# ReactionGame.net
KiCad netlist of a schematic drawn in EAGLE
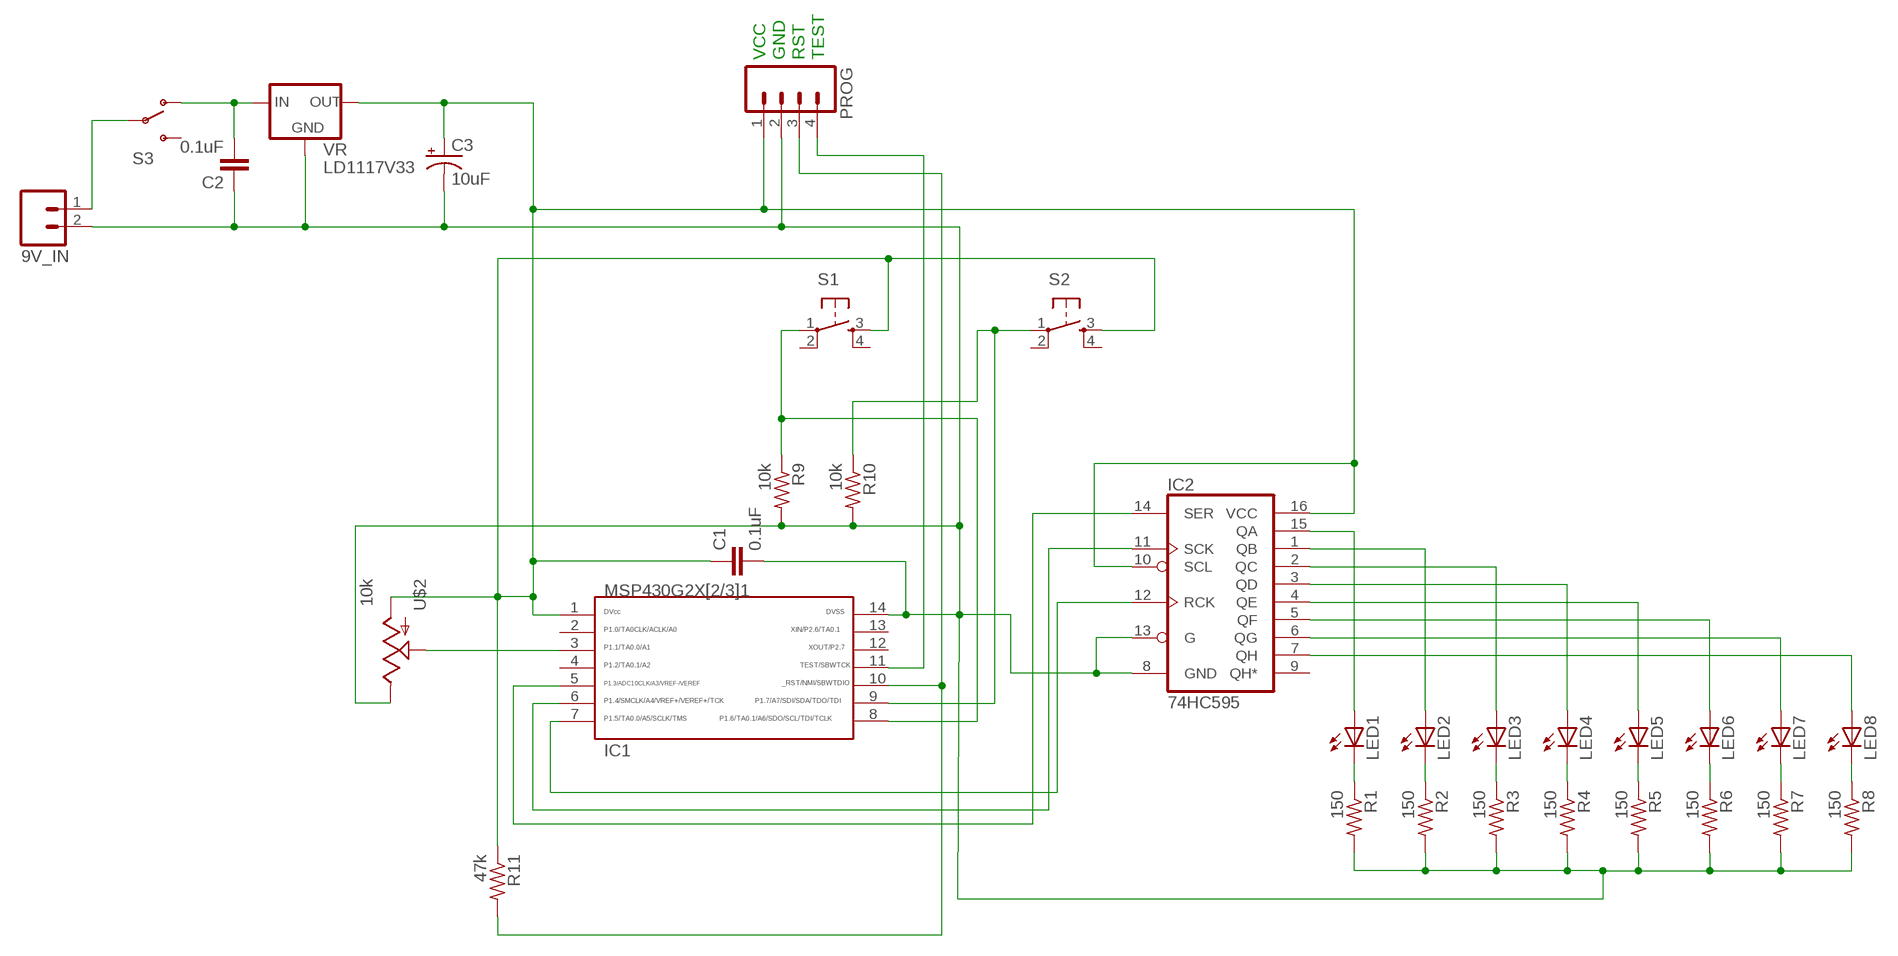
[diagram p0: schematic, sheet 1]

(export (version "E")
  (design (tool "Eeschema 10.0.6"))
  (components
    (comp (ref "9V_IN")
      (value "M02PTH3")
      (footprint "eagle-import:1X02_LONGPADS")
      (libsource (lib "eagle-import") (part "M02PTH3"))
    )
    (comp (ref "C1")
      (value "0.1uF")
      (footprint "eagle-import:CAP-PTH-SMALL2")
      (libsource (lib "eagle-import") (part "CAPPTH2"))
    )
    (comp (ref "C2")
      (value "0.1uF")
      (footprint "eagle-import:CAP-PTH-SMALL2")
      (libsource (lib "eagle-import") (part "CAPPTH2"))
    )
    (comp (ref "C3")
      (value "10uF")
      (footprint "eagle-import:CPOL-RADIAL-100UF-25V")
      (libsource (lib "eagle-import") (part "CAP_POLPTH1"))
    )
    (comp (ref "IC1")
      (value "MSP430G2231")
      (footprint "eagle-import:N14")
      (libsource (lib "eagle-import") (part "G2X[2/3]1---N14"))
    )
    (comp (ref "IC2")
      (value "74HC595")
      (footprint "eagle-import:DIL16")
      (libsource (lib "eagle-import") (part "74595NLS"))
    )
    (comp (ref "LED1")
      (value "LED5MM")
      (footprint "eagle-import:LED5MM")
      (libsource (lib "eagle-import") (part "LED5MM"))
    )
    (comp (ref "LED2")
      (value "LED5MM")
      (footprint "eagle-import:LED5MM")
      (libsource (lib "eagle-import") (part "LED5MM"))
    )
    (comp (ref "LED3")
      (value "LED5MM")
      (footprint "eagle-import:LED5MM")
      (libsource (lib "eagle-import") (part "LED5MM"))
    )
    (comp (ref "LED4")
      (value "LED5MM")
      (footprint "eagle-import:LED5MM")
      (libsource (lib "eagle-import") (part "LED5MM"))
    )
    (comp (ref "LED5")
      (value "LED5MM")
      (footprint "eagle-import:LED5MM")
      (libsource (lib "eagle-import") (part "LED5MM"))
    )
    (comp (ref "LED6")
      (value "LED5MM")
      (footprint "eagle-import:LED5MM")
      (libsource (lib "eagle-import") (part "LED5MM"))
    )
    (comp (ref "LED7")
      (value "LED5MM")
      (footprint "eagle-import:LED5MM")
      (libsource (lib "eagle-import") (part "LED5MM"))
    )
    (comp (ref "LED8")
      (value "LED5MM")
      (footprint "eagle-import:LED5MM")
      (libsource (lib "eagle-import") (part "LED5MM"))
    )
    (comp (ref "PROG")
      (value "M04LOCK")
      (footprint "eagle-import:1X04_LOCK")
      (libsource (lib "eagle-import") (part "M04LOCK"))
    )
    (comp (ref "R1")
      (value "150")
      (footprint "eagle-import:0207_10")
      (libsource (lib "eagle-import") (part "R-US_0207/10"))
    )
    (comp (ref "R2")
      (value "150")
      (footprint "eagle-import:0207_10")
      (libsource (lib "eagle-import") (part "R-US_0207/10"))
    )
    (comp (ref "R3")
      (value "150")
      (footprint "eagle-import:0207_10")
      (libsource (lib "eagle-import") (part "R-US_0207/10"))
    )
    (comp (ref "R4")
      (value "150")
      (footprint "eagle-import:0207_10")
      (libsource (lib "eagle-import") (part "R-US_0207/10"))
    )
    (comp (ref "R5")
      (value "150")
      (footprint "eagle-import:0207_10")
      (libsource (lib "eagle-import") (part "R-US_0207/10"))
    )
    (comp (ref "R6")
      (value "150")
      (footprint "eagle-import:0207_10")
      (libsource (lib "eagle-import") (part "R-US_0207/10"))
    )
    (comp (ref "R7")
      (value "150")
      (footprint "eagle-import:0207_10")
      (libsource (lib "eagle-import") (part "R-US_0207/10"))
    )
    (comp (ref "R8")
      (value "150")
      (footprint "eagle-import:0207_10")
      (libsource (lib "eagle-import") (part "R-US_0207/10"))
    )
    (comp (ref "R9")
      (value "10k")
      (footprint "eagle-import:0207_10")
      (libsource (lib "eagle-import") (part "R-US_0207/10"))
    )
    (comp (ref "R10")
      (value "10k")
      (footprint "eagle-import:0207_10")
      (libsource (lib "eagle-import") (part "R-US_0207/10"))
    )
    (comp (ref "R11")
      (value "47k")
      (footprint "eagle-import:0207_10")
      (libsource (lib "eagle-import") (part "R-US_0207/10"))
    )
    (comp (ref "S1")
      (value "TAC_SWITCHPTH")
      (footprint "eagle-import:TACTILE-PTH")
      (libsource (lib "eagle-import") (part "TAC_SWITCHPTH"))
    )
    (comp (ref "S2")
      (value "TAC_SWITCHPTH")
      (footprint "eagle-import:TACTILE-PTH")
      (libsource (lib "eagle-import") (part "TAC_SWITCHPTH"))
    )
    (comp (ref "S3")
      (value "SWITCH-SPSTKIT")
      (footprint "eagle-import:SWITCH-SPDT_KIT")
      (libsource (lib "eagle-import") (part "SWITCH-SPSTKIT"))
    )
    (comp (ref "U$2")
      (value "10k")
      (footprint "eagle-import:ALPS_POT")
      (libsource (lib "eagle-import") (part "POT"))
    )
    (comp (ref "VR")
      (value "LD1117V33")
      (footprint "eagle-import:78XXL")
      (libsource (lib "eagle-import") (part "V_REG_LD1117VXX"))
    )
  )
  (nets
    (net (code "1") (name "Net-(C3-+)") (class "Default")
      (node (ref "C1") (pin "1") (pinfunction "1_1") (pintype "passive"))
      (node (ref "C3") (pin "1") (pinfunction "+_1") (pintype "passive"))
      (node (ref "IC1") (pin "1") (pinfunction "1_1") (pintype "bidirectional"))
      (node (ref "IC2") (pin "10") (pinfunction "SCL_10") (pintype "input"))
      (node (ref "IC2") (pin "16") (pinfunction "VCC_16") (pintype "power_in"))
      (node (ref "PROG") (pin "1") (pinfunction "1_1") (pintype "passive"))
      (node (ref "R11") (pin "1") (pinfunction "1_1") (pintype "passive"))
      (node (ref "S1") (pin "3") (pinfunction "3_3") (pintype "passive"))
      (node (ref "S2") (pin "3") (pinfunction "3_3") (pintype "passive"))
      (node (ref "U$2") (pin "P$3") (pinfunction "A_P$3") (pintype "passive"))
      (node (ref "VR") (pin "GND") (pinfunction "OUT_GND") (pintype "output"))
    )
    (net (code "2") (name "Net-(C3--)") (class "Default")
      (node (ref "9V_IN") (pin "2") (pinfunction "2_2") (pintype "passive"))
      (node (ref "C1") (pin "2") (pinfunction "2_2") (pintype "passive"))
      (node (ref "C2") (pin "1") (pinfunction "1_1") (pintype "passive"))
      (node (ref "C3") (pin "2") (pinfunction "-_2") (pintype "passive"))
      (node (ref "IC1") (pin "14") (pinfunction "14_14") (pintype "bidirectional"))
      (node (ref "IC2") (pin "13") (pinfunction "G_13") (pintype "input"))
      (node (ref "IC2") (pin "8") (pinfunction "GND_8") (pintype "power_in"))
      (node (ref "PROG") (pin "2") (pinfunction "2_2") (pintype "passive"))
      (node (ref "R1") (pin "2") (pinfunction "2_2") (pintype "passive"))
      (node (ref "R10") (pin "2") (pinfunction "2_2") (pintype "passive"))
      (node (ref "R2") (pin "2") (pinfunction "2_2") (pintype "passive"))
      (node (ref "R3") (pin "2") (pinfunction "2_2") (pintype "passive"))
      (node (ref "R4") (pin "2") (pinfunction "2_2") (pintype "passive"))
      (node (ref "R5") (pin "2") (pinfunction "2_2") (pintype "passive"))
      (node (ref "R6") (pin "2") (pinfunction "2_2") (pintype "passive"))
      (node (ref "R7") (pin "2") (pinfunction "2_2") (pintype "passive"))
      (node (ref "R8") (pin "2") (pinfunction "2_2") (pintype "passive"))
      (node (ref "R9") (pin "2") (pinfunction "2_2") (pintype "passive"))
      (node (ref "U$2") (pin "P$1") (pinfunction "E_P$1") (pintype "passive"))
      (node (ref "VR") (pin "IN") (pinfunction "GND_IN") (pintype "input"))
    )
    (net (code "3") (name "Net-(IC1-Pad8)") (class "Default")
      (node (ref "IC1") (pin "8") (pinfunction "8_8") (pintype "bidirectional"))
      (node (ref "R9") (pin "1") (pinfunction "1_1") (pintype "passive"))
      (node (ref "S1") (pin "1") (pinfunction "1_1") (pintype "passive"))
    )
    (net (code "4") (name "Net-(IC1-Pad9)") (class "Default")
      (node (ref "IC1") (pin "9") (pinfunction "9_9") (pintype "bidirectional"))
      (node (ref "R10") (pin "1") (pinfunction "1_1") (pintype "passive"))
      (node (ref "S2") (pin "1") (pinfunction "1_1") (pintype "passive"))
    )
    (net (code "5") (name "Net-(IC1-Pad10)") (class "Default")
      (node (ref "IC1") (pin "10") (pinfunction "10_10") (pintype "bidirectional"))
      (node (ref "PROG") (pin "3") (pinfunction "3_3") (pintype "passive"))
      (node (ref "R11") (pin "2") (pinfunction "2_2") (pintype "passive"))
    )
    (net (code "6") (name "Net-(IC1-Pad11)") (class "Default")
      (node (ref "IC1") (pin "11") (pinfunction "11_11") (pintype "bidirectional"))
      (node (ref "PROG") (pin "4") (pinfunction "4_4") (pintype "passive"))
    )
    (net (code "7") (name "Net-(IC2-QA)") (class "Default")
      (node (ref "IC2") (pin "15") (pinfunction "QA_15") (pintype "tri_state"))
      (node (ref "LED1") (pin "A") (pinfunction "A_A") (pintype "passive"))
    )
    (net (code "8") (name "Net-(IC2-QB)") (class "Default")
      (node (ref "IC2") (pin "1") (pinfunction "QB_1") (pintype "tri_state"))
      (node (ref "LED2") (pin "A") (pinfunction "A_A") (pintype "passive"))
    )
    (net (code "9") (name "Net-(IC2-QC)") (class "Default")
      (node (ref "IC2") (pin "2") (pinfunction "QC_2") (pintype "tri_state"))
      (node (ref "LED3") (pin "A") (pinfunction "A_A") (pintype "passive"))
    )
    (net (code "10") (name "Net-(IC2-QD)") (class "Default")
      (node (ref "IC2") (pin "3") (pinfunction "QD_3") (pintype "tri_state"))
      (node (ref "LED4") (pin "A") (pinfunction "A_A") (pintype "passive"))
    )
    (net (code "11") (name "Net-(IC2-QE)") (class "Default")
      (node (ref "IC2") (pin "4") (pinfunction "QE_4") (pintype "tri_state"))
      (node (ref "LED5") (pin "A") (pinfunction "A_A") (pintype "passive"))
    )
    (net (code "12") (name "Net-(IC2-QF)") (class "Default")
      (node (ref "IC2") (pin "5") (pinfunction "QF_5") (pintype "tri_state"))
      (node (ref "LED6") (pin "A") (pinfunction "A_A") (pintype "passive"))
    )
    (net (code "13") (name "Net-(IC2-QG)") (class "Default")
      (node (ref "IC2") (pin "6") (pinfunction "QG_6") (pintype "tri_state"))
      (node (ref "LED7") (pin "A") (pinfunction "A_A") (pintype "passive"))
    )
    (net (code "14") (name "Net-(IC2-QH)") (class "Default")
      (node (ref "IC2") (pin "7") (pinfunction "QH_7") (pintype "tri_state"))
      (node (ref "LED8") (pin "A") (pinfunction "A_A") (pintype "passive"))
    )
    (net (code "15") (name "Net-(IC2-RCK)") (class "Default")
      (node (ref "IC1") (pin "7") (pinfunction "7_7") (pintype "bidirectional"))
      (node (ref "IC2") (pin "12") (pinfunction "RCK_12") (pintype "input"))
    )
    (net (code "16") (name "Net-(IC2-SCK)") (class "Default")
      (node (ref "IC1") (pin "6") (pinfunction "6_6") (pintype "bidirectional"))
      (node (ref "IC2") (pin "11") (pinfunction "SCK_11") (pintype "input"))
    )
    (net (code "17") (name "Net-(IC2-SER)") (class "Default")
      (node (ref "IC1") (pin "5") (pinfunction "5_5") (pintype "bidirectional"))
      (node (ref "IC2") (pin "14") (pinfunction "SER_14") (pintype "input"))
    )
    (net (code "18") (name "Net-(LED1-C)") (class "Default")
      (node (ref "LED1") (pin "K") (pinfunction "C_K") (pintype "passive"))
      (node (ref "R1") (pin "1") (pinfunction "1_1") (pintype "passive"))
    )
    (net (code "19") (name "Net-(LED2-C)") (class "Default")
      (node (ref "LED2") (pin "K") (pinfunction "C_K") (pintype "passive"))
      (node (ref "R2") (pin "1") (pinfunction "1_1") (pintype "passive"))
    )
    (net (code "20") (name "Net-(LED3-C)") (class "Default")
      (node (ref "LED3") (pin "K") (pinfunction "C_K") (pintype "passive"))
      (node (ref "R3") (pin "1") (pinfunction "1_1") (pintype "passive"))
    )
    (net (code "21") (name "Net-(LED4-C)") (class "Default")
      (node (ref "LED4") (pin "K") (pinfunction "C_K") (pintype "passive"))
      (node (ref "R4") (pin "1") (pinfunction "1_1") (pintype "passive"))
    )
    (net (code "22") (name "Net-(LED5-C)") (class "Default")
      (node (ref "LED5") (pin "K") (pinfunction "C_K") (pintype "passive"))
      (node (ref "R5") (pin "1") (pinfunction "1_1") (pintype "passive"))
    )
    (net (code "23") (name "Net-(LED6-C)") (class "Default")
      (node (ref "LED6") (pin "K") (pinfunction "C_K") (pintype "passive"))
      (node (ref "R6") (pin "1") (pinfunction "1_1") (pintype "passive"))
    )
    (net (code "24") (name "Net-(LED7-C)") (class "Default")
      (node (ref "LED7") (pin "K") (pinfunction "C_K") (pintype "passive"))
      (node (ref "R7") (pin "1") (pinfunction "1_1") (pintype "passive"))
    )
    (net (code "25") (name "Net-(LED8-C)") (class "Default")
      (node (ref "LED8") (pin "K") (pinfunction "C_K") (pintype "passive"))
      (node (ref "R8") (pin "1") (pinfunction "1_1") (pintype "passive"))
    )
    (net (code "26") (name "Net-(S3-O)") (class "Default")
      (node (ref "C2") (pin "2") (pinfunction "2_2") (pintype "passive"))
      (node (ref "S3") (pin "1") (pinfunction "O_1") (pintype "passive"))
      (node (ref "VR") (pin "OUT") (pinfunction "IN_OUT") (pintype "input"))
    )
    (net (code "27") (name "Net-(S3-P)") (class "Default")
      (node (ref "9V_IN") (pin "1") (pinfunction "1_1") (pintype "passive"))
      (node (ref "S3") (pin "2") (pinfunction "P_2") (pintype "passive"))
    )
    (net (code "28") (name "Net-(U$2-S)") (class "Default")
      (node (ref "IC1") (pin "3") (pinfunction "3_3") (pintype "bidirectional"))
      (node (ref "U$2") (pin "P$2") (pinfunction "S_P$2") (pintype "passive"))
    )
    (net (code "29") (name "unconnected-(IC1-Pad2)") (class "Default")
      (node (ref "IC1") (pin "2") (pinfunction "2_2") (pintype "bidirectional"))
    )
    (net (code "30") (name "unconnected-(IC1-Pad4)") (class "Default")
      (node (ref "IC1") (pin "4") (pinfunction "4_4") (pintype "bidirectional"))
    )
    (net (code "31") (name "unconnected-(IC1-Pad12)") (class "Default")
      (node (ref "IC1") (pin "12") (pinfunction "12_12") (pintype "bidirectional"))
    )
    (net (code "32") (name "unconnected-(IC1-Pad13)") (class "Default")
      (node (ref "IC1") (pin "13") (pinfunction "13_13") (pintype "bidirectional"))
    )
    (net (code "33") (name "unconnected-(IC2-QH*-Pad9)") (class "Default")
      (node (ref "IC2") (pin "9") (pinfunction "QH*_9") (pintype "tri_state"))
    )
    (net (code "34") (name "unconnected-(S1-Pad2)") (class "Default")
      (node (ref "S1") (pin "2") (pinfunction "2_2") (pintype "passive"))
    )
    (net (code "35") (name "unconnected-(S1-Pad4)") (class "Default")
      (node (ref "S1") (pin "4") (pinfunction "4_4") (pintype "passive"))
    )
    (net (code "36") (name "unconnected-(S2-Pad2)") (class "Default")
      (node (ref "S2") (pin "2") (pinfunction "2_2") (pintype "passive"))
    )
    (net (code "37") (name "unconnected-(S2-Pad4)") (class "Default")
      (node (ref "S2") (pin "4") (pinfunction "4_4") (pintype "passive"))
    )
    (net (code "38") (name "unconnected-(S3-S-Pad3)") (class "Default")
      (node (ref "S3") (pin "3") (pinfunction "S_3") (pintype "passive"))
    )
  )
)
